# x-IMU3-SA-TRRS.net
KiCad netlist of a schematic drawn in Altium Designer
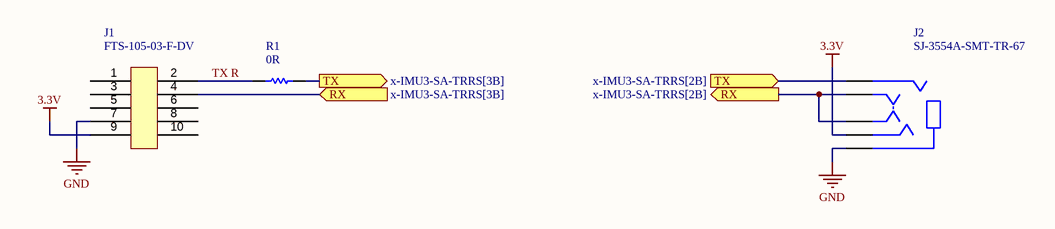
[diagram p0: x-IMU3-SA-TRRS.SchDoc]

(export (version "E")
  (design (tool "Eeschema 10.0.6"))
  (components
    (comp (ref "J1")
      (value "FTS-105-03-F-DV")
      (footprint "FTS-105-03-F-DV")
      (libsource (lib "x-io") (part "FTS-105-03-F-DV"))
    )
    (comp (ref "J2")
      (value "SJ-3554A-SMT-TR-67")
      (footprint "SJ-3554A-SMT-TR-67")
      (libsource (lib "x-io") (part "SJ-3554A-SMT-TR-67"))
    )
    (comp (ref "R1") (value "0R") (footprint "Resistor 0603") (libsource (lib "x-io") (part "Resistor")))
  )
  (nets
    (net (code "1") (name "/RX") (class "Default")
      (node (ref "J1") (pin "4") (pinfunction "*_4") (pintype "passive"))
      (node (ref "J2") (pin "2") (pinfunction "tip_2") (pintype "passive"))
      (node (ref "J2") (pin "5") (pinfunction "tip_5") (pintype "passive"))
    )
    (net (code "2") (name "/TX") (class "Default")
      (node (ref "J2") (pin "4") (pinfunction "ring_2_4") (pintype "passive"))
      (node (ref "R1") (pin "2") (pinfunction "2_2") (pintype "passive"))
    )
    (net (code "3") (name "/TX R") (class "Default")
      (node (ref "J1") (pin "2") (pinfunction "*_2") (pintype "passive"))
      (node (ref "R1") (pin "1") (pinfunction "1_1") (pintype "passive"))
    )
    (net (code "4") (name "3.3V") (class "Default")
      (node (ref "J1") (pin "9") (pinfunction "*_9") (pintype "passive"))
      (node (ref "J2") (pin "3") (pinfunction "ring_1_3") (pintype "passive"))
    )
    (net (code "5") (name "GND") (class "Default")
      (node (ref "J1") (pin "7") (pinfunction "*_7") (pintype "passive"))
      (node (ref "J2") (pin "1") (pinfunction "sleeve_1") (pintype "passive"))
    )
    (net (code "6") (name "unconnected-(J1-*-Pad1)") (class "Default")
      (node (ref "J1") (pin "1") (pinfunction "*_1") (pintype "passive"))
    )
    (net (code "7") (name "unconnected-(J1-*-Pad3)") (class "Default")
      (node (ref "J1") (pin "3") (pinfunction "*_3") (pintype "passive"))
    )
    (net (code "8") (name "unconnected-(J1-*-Pad5)") (class "Default")
      (node (ref "J1") (pin "5") (pinfunction "*_5") (pintype "passive"))
    )
    (net (code "9") (name "unconnected-(J1-*-Pad6)") (class "Default")
      (node (ref "J1") (pin "6") (pinfunction "*_6") (pintype "passive"))
    )
    (net (code "10") (name "unconnected-(J1-*-Pad8)") (class "Default")
      (node (ref "J1") (pin "8") (pinfunction "*_8") (pintype "passive"))
    )
    (net (code "11") (name "unconnected-(J1-*-Pad10)") (class "Default")
      (node (ref "J1") (pin "10") (pinfunction "*_10") (pintype "passive"))
    )
  )
)
